# SCH_IV_Project_2025-03-30.net
KiCad netlist of a schematic drawn in EasyEDA
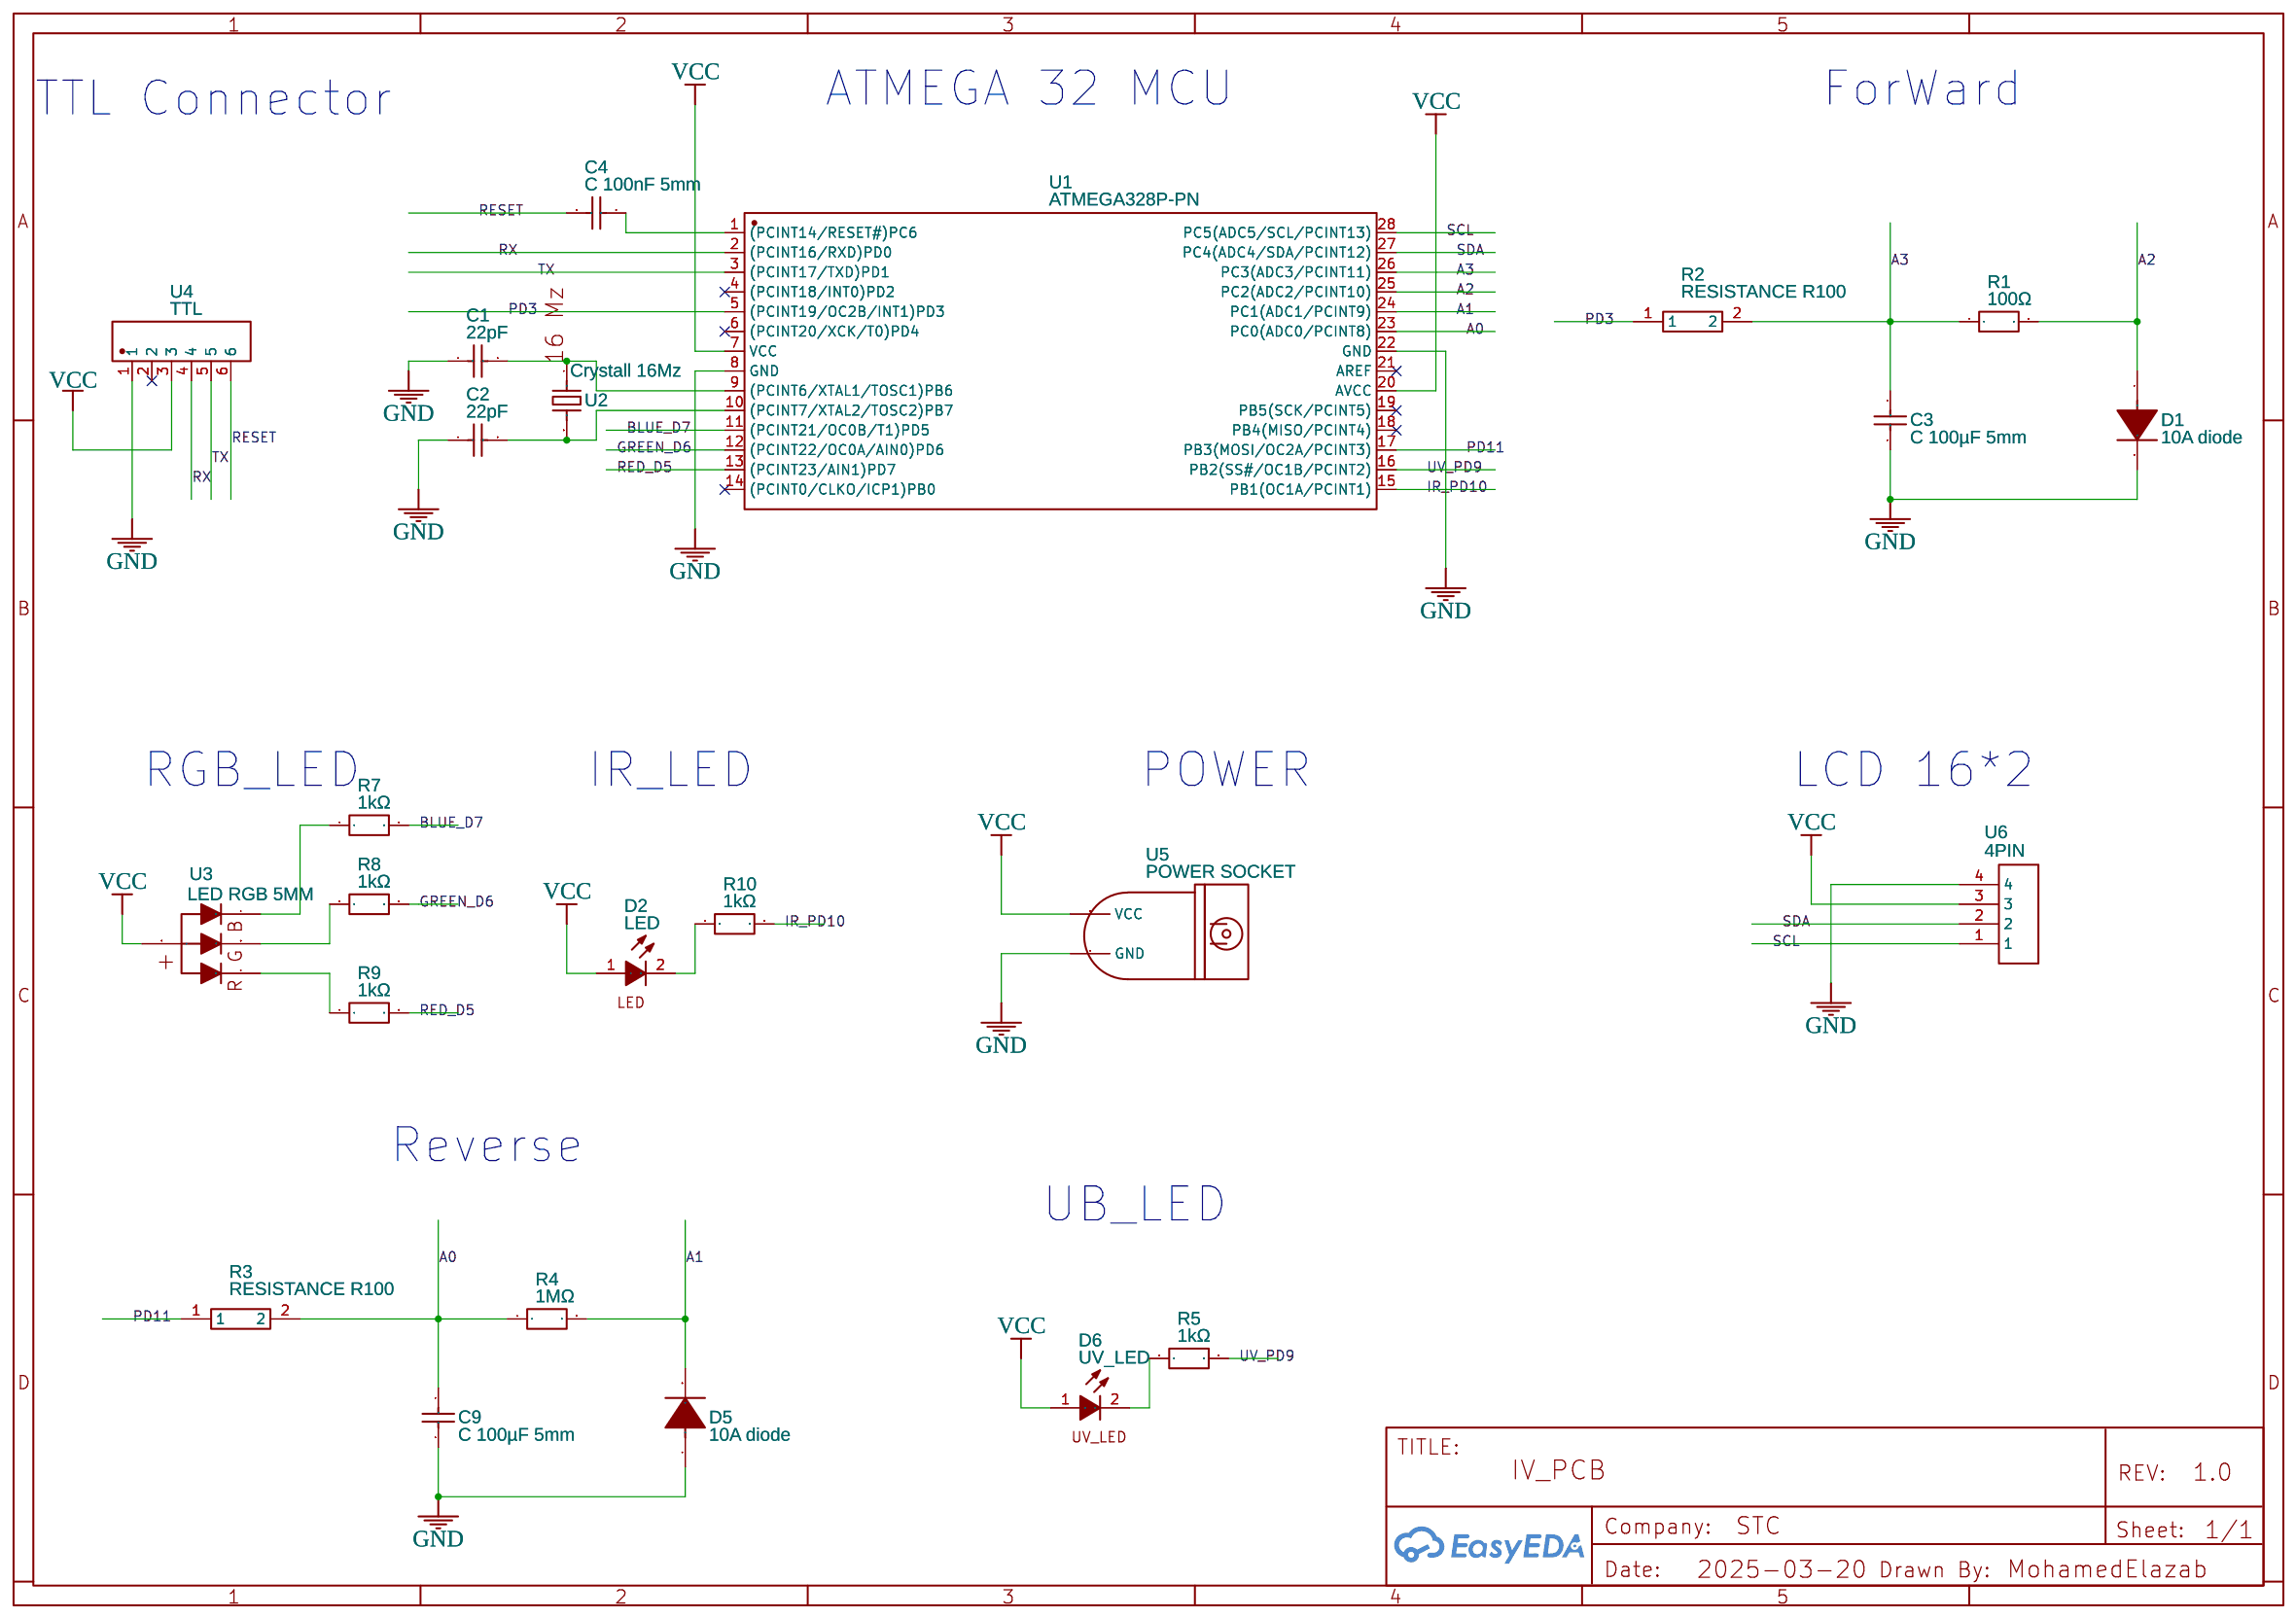
[diagram p0: schematic sheet]

(export (version "E")
  (design (tool "Eeschema 10.0.6"))
  (components
    (comp (ref "C1")
      (value "22pF")
      (fields (field (name "Manufacturer Part") "22pf/50V 10%") (field (name "Manufacturer") "ReliaPro"))
      (libsource (lib "") (part "22pf/50V 10%"))
    )
    (comp (ref "C2")
      (value "22pF")
      (fields (field (name "Manufacturer Part") "22pf/50V 10%") (field (name "Manufacturer") "ReliaPro"))
      (libsource (lib "") (part "22pf/50V 10%"))
    )
    (comp (ref "C3")
      (value "C 100µF 5mm")
      (fields (field (name "Manufacturer Part") "0.1UF(104) +-20% 63v") (field (name "Manufacturer") "LCSC"))
      (libsource (lib "") (part "C 100nF 5mm_1"))
    )
    (comp (ref "C4")
      (value "C 100nF 5mm")
      (fields (field (name "Manufacturer Part") "0.1UF(104) +-20% 63v") (field (name "Manufacturer") "LCSC"))
      (libsource (lib "") (part "C 100nF 5mm"))
    )
    (comp (ref "C9")
      (value "C 100µF 5mm")
      (fields (field (name "Manufacturer Part") "0.1UF(104) +-20% 63v") (field (name "Manufacturer") "LCSC"))
      (libsource (lib "") (part "C 100nF 5mm_1"))
    )
    (comp (ref "D1")
      (value "10A diode")
      (fields (field (name "Manufacturer Part") "10A10") (field (name "Manufacturer") "ST(先科)"))
      (libsource (lib "") (part "10A diode_1"))
    )
    (comp (ref "D2")
      (value "LED")
      (fields (field (name "Manufacturer Part") "5600") (field (name "Manufacturer") "VccLite"))
      (libsource (lib "") (part "LED_1"))
    )
    (comp (ref "D5")
      (value "10A diode")
      (fields (field (name "Manufacturer Part") "10A10") (field (name "Manufacturer") "ST(先科)"))
      (libsource (lib "") (part "10A diode"))
    )
    (comp (ref "D6")
      (value "UV_LED")
      (fields (field (name "Manufacturer Part") "5600") (field (name "Manufacturer") "VccLite"))
      (libsource (lib "") (part "LED"))
    )
    (comp (ref "R1")
      (value "100Ω")
      (fields (field (name "Manufacturer Part") "MFR50SFBE52-1K") (field (name "Manufacturer") "YAGEO(国巨)"))
      (libsource (lib "") (part "MFR50SFBE52-1K"))
    )
    (comp (ref "R2") (value "RESISTANCE R100") (libsource (lib "") (part "RESISTANCE R100")))
    (comp (ref "R3") (value "RESISTANCE R100") (libsource (lib "") (part "RESISTANCE R100")))
    (comp (ref "R4")
      (value "1MΩ")
      (fields (field (name "Manufacturer Part") "MFR50SFBE52-1K") (field (name "Manufacturer") "YAGEO(国巨)"))
      (libsource (lib "") (part "MFR50SFBE52-1K"))
    )
    (comp (ref "R5")
      (value "1kΩ")
      (fields (field (name "Manufacturer Part") "MFR50SFBE52-1K") (field (name "Manufacturer") "YAGEO(国巨)"))
      (libsource (lib "") (part "MFR50SFBE52-1K"))
    )
    (comp (ref "R7")
      (value "1kΩ")
      (fields (field (name "Manufacturer Part") "MFR50SFBE52-1K") (field (name "Manufacturer") "YAGEO(国巨)"))
      (libsource (lib "") (part "MFR50SFBE52-1K"))
    )
    (comp (ref "R8")
      (value "1kΩ")
      (fields (field (name "Manufacturer Part") "MFR50SFBE52-1K") (field (name "Manufacturer") "YAGEO(国巨)"))
      (libsource (lib "") (part "MFR50SFBE52-1K"))
    )
    (comp (ref "R9")
      (value "1kΩ")
      (fields (field (name "Manufacturer Part") "MFR50SFBE52-1K") (field (name "Manufacturer") "YAGEO(国巨)"))
      (libsource (lib "") (part "MFR50SFBE52-1K"))
    )
    (comp (ref "R10")
      (value "1kΩ")
      (fields (field (name "Manufacturer Part") "MFR50SFBE52-1K") (field (name "Manufacturer") "YAGEO(国巨)"))
      (libsource (lib "") (part "MFR50SFBE52-1K"))
    )
    (comp (ref "U1")
      (value "ATMEGA328P-PN")
      (fields (field (name "Manufacturer") "MICROCHIP(美国微芯)"))
      (libsource (lib "") (part "ATMEGA328P-PN"))
    )
    (comp (ref "U2") (value "Crystall 16Mz") (libsource (lib "") (part "Crystall 16Mz")))
    (comp (ref "U3") (value "LED RGB 5MM") (libsource (lib "") (part "LED RGB 5MM (ARL5RGB) EDIT")))
    (comp (ref "U4")
      (value "TTL")
      (fields (field (name "Manufacturer Part") "DS1021-1x6SF11-B") (field (name "Manufacturer") "CONNFLY"))
      (libsource (lib "") (part "DS1021-1X6SF11-B"))
    )
    (comp (ref "U5") (value "POWER SOCKET") (libsource (lib "") (part "POWER SOCKET")))
    (comp (ref "U6") (value "4PIN") (libsource (lib "") (part "4PIN")))
  )
  (nets
    (net (code "1") (name "/A0") (class "Default")
      (node (ref "C9") (pin "1") (pinfunction "1_1") (pintype "input"))
      (node (ref "R3") (pin "2") (pinfunction "2_2") (pintype "unspecified"))
      (node (ref "R4") (pin "1") (pinfunction "1_1") (pintype "unspecified"))
      (node (ref "U1") (pin "23") (pinfunction "PC0(ADC0/PCINT8)_23") (pintype "unspecified"))
    )
    (net (code "2") (name "/A1") (class "Default")
      (node (ref "D5") (pin "2") (pinfunction "K_2") (pintype "unspecified"))
      (node (ref "R4") (pin "2") (pinfunction "2_2") (pintype "unspecified"))
      (node (ref "U1") (pin "24") (pinfunction "PC1(ADC1/PCINT9)_24") (pintype "unspecified"))
    )
    (net (code "3") (name "/A2") (class "Default")
      (node (ref "D1") (pin "1") (pinfunction "A_1") (pintype "unspecified"))
      (node (ref "R1") (pin "2") (pinfunction "2_2") (pintype "unspecified"))
      (node (ref "U1") (pin "25") (pinfunction "PC2(ADC2/PCINT10)_25") (pintype "unspecified"))
    )
    (net (code "4") (name "/A3") (class "Default")
      (node (ref "C3") (pin "1") (pinfunction "1_1") (pintype "input"))
      (node (ref "R1") (pin "1") (pinfunction "1_1") (pintype "unspecified"))
      (node (ref "R2") (pin "2") (pinfunction "2_2") (pintype "unspecified"))
      (node (ref "U1") (pin "26") (pinfunction "PC3(ADC3/PCINT11)_26") (pintype "unspecified"))
    )
    (net (code "5") (name "/BLUE_D7") (class "Default")
      (node (ref "R7") (pin "2") (pinfunction "2_2") (pintype "unspecified"))
      (node (ref "U1") (pin "11") (pinfunction "(PCINT21/OC0B/T1)PD5_11") (pintype "unspecified"))
    )
    (net (code "6") (name "/GREEN_D6") (class "Default")
      (node (ref "R8") (pin "2") (pinfunction "2_2") (pintype "unspecified"))
      (node (ref "U1") (pin "12") (pinfunction "(PCINT22/OC0A/AIN0)PD6_12") (pintype "unspecified"))
    )
    (net (code "7") (name "/IR_PD10") (class "Default")
      (node (ref "R10") (pin "2") (pinfunction "2_2") (pintype "unspecified"))
      (node (ref "U1") (pin "15") (pinfunction "PB1(OC1A/PCINT1)_15") (pintype "unspecified"))
    )
    (net (code "8") (name "/PD3") (class "Default")
      (node (ref "R2") (pin "1") (pinfunction "1_1") (pintype "unspecified"))
      (node (ref "U1") (pin "5") (pinfunction "(PCINT19/OC2B/INT1)PD3_5") (pintype "unspecified"))
    )
    (net (code "9") (name "/PD11") (class "Default")
      (node (ref "R3") (pin "1") (pinfunction "1_1") (pintype "unspecified"))
      (node (ref "U1") (pin "17") (pinfunction "PB3(MOSI/OC2A/PCINT3)_17") (pintype "unspecified"))
    )
    (net (code "10") (name "/RED_D5") (class "Default")
      (node (ref "R9") (pin "2") (pinfunction "2_2") (pintype "unspecified"))
      (node (ref "U1") (pin "13") (pinfunction "(PCINT23/AIN1)PD7_13") (pintype "unspecified"))
    )
    (net (code "11") (name "/RESET") (class "Default")
      (node (ref "C4") (pin "1") (pinfunction "1_1") (pintype "input"))
      (node (ref "U4") (pin "6") (pinfunction "6_6") (pintype "unspecified"))
    )
    (net (code "12") (name "/RX") (class "Default")
      (node (ref "U1") (pin "2") (pinfunction "(PCINT16/RXD)PD0_2") (pintype "unspecified"))
      (node (ref "U4") (pin "4") (pinfunction "4_4") (pintype "unspecified"))
    )
    (net (code "13") (name "/SCL") (class "Default")
      (node (ref "U1") (pin "28") (pinfunction "PC5(ADC5/SCL/PCINT13)_28") (pintype "unspecified"))
      (node (ref "U6") (pin "1") (pinfunction "1_1") (pintype "unspecified"))
    )
    (net (code "14") (name "/SDA") (class "Default")
      (node (ref "U1") (pin "27") (pinfunction "PC4(ADC4/SDA/PCINT12)_27") (pintype "unspecified"))
      (node (ref "U6") (pin "2") (pinfunction "2_2") (pintype "unspecified"))
    )
    (net (code "15") (name "/TX") (class "Default")
      (node (ref "U1") (pin "3") (pinfunction "(PCINT17/TXD)PD1_3") (pintype "unspecified"))
      (node (ref "U4") (pin "5") (pinfunction "5_5") (pintype "unspecified"))
    )
    (net (code "16") (name "/UV_PD9") (class "Default")
      (node (ref "R5") (pin "2") (pinfunction "2_2") (pintype "unspecified"))
      (node (ref "U1") (pin "16") (pinfunction "PB2(SS#/OC1B/PCINT2)_16") (pintype "unspecified"))
    )
    (net (code "17") (name "GND") (class "Default")
      (node (ref "C1") (pin "1") (pinfunction "1_1") (pintype "input"))
      (node (ref "C2") (pin "1") (pinfunction "1_1") (pintype "input"))
      (node (ref "C3") (pin "2") (pinfunction "2_2") (pintype "input"))
      (node (ref "C9") (pin "2") (pinfunction "2_2") (pintype "input"))
      (node (ref "D1") (pin "2") (pinfunction "K_2") (pintype "unspecified"))
      (node (ref "D5") (pin "1") (pinfunction "A_1") (pintype "unspecified"))
      (node (ref "U1") (pin "22") (pinfunction "GND_22") (pintype "unspecified"))
      (node (ref "U1") (pin "8") (pinfunction "GND_8") (pintype "unspecified"))
      (node (ref "U4") (pin "1") (pinfunction "1_1") (pintype "unspecified"))
      (node (ref "U5") (pin "2") (pinfunction "GND_2") (pintype "passive"))
      (node (ref "U6") (pin "4") (pinfunction "4_4") (pintype "unspecified"))
    )
    (net (code "18") (name "Net-(D2-K)") (class "Default")
      (node (ref "D2") (pin "2") (pinfunction "K_2") (pintype "input"))
      (node (ref "R10") (pin "1") (pinfunction "1_1") (pintype "unspecified"))
    )
    (net (code "19") (name "Net-(D6-K)") (class "Default")
      (node (ref "D6") (pin "2") (pinfunction "K_2") (pintype "input"))
      (node (ref "R5") (pin "1") (pinfunction "1_1") (pintype "unspecified"))
    )
    (net (code "20") (name "Net-(R9-Pad1)") (class "Default")
      (node (ref "R9") (pin "1") (pinfunction "1_1") (pintype "unspecified"))
      (node (ref "U3") (pin "1") (pinfunction "1_1") (pintype "unspecified"))
    )
    (net (code "21") (name "Net-(U1-(PCINT6{slash}XTAL1{slash}TOSC1)PB6)") (class "Default")
      (node (ref "C1") (pin "2") (pinfunction "2_2") (pintype "input"))
      (node (ref "U1") (pin "9") (pinfunction "(PCINT6/XTAL1/TOSC1)PB6_9") (pintype "unspecified"))
      (node (ref "U2") (pin "1") (pinfunction "1_1") (pintype "input"))
    )
    (net (code "22") (name "Net-(U1-(PCINT7{slash}XTAL2{slash}TOSC2)PB7)") (class "Default")
      (node (ref "C2") (pin "2") (pinfunction "2_2") (pintype "input"))
      (node (ref "U1") (pin "10") (pinfunction "(PCINT7/XTAL2/TOSC2)PB7_10") (pintype "unspecified"))
      (node (ref "U2") (pin "2") (pinfunction "2_2") (pintype "input"))
    )
    (net (code "23") (name "Net-(U1-(PCINT14{slash}RESET#)PC6)") (class "Default")
      (node (ref "C4") (pin "2") (pinfunction "2_2") (pintype "input"))
      (node (ref "U1") (pin "1") (pinfunction "(PCINT14/RESET#)PC6_1") (pintype "unspecified"))
    )
    (net (code "24") (name "Net-(U3-2)") (class "Default")
      (node (ref "R8") (pin "1") (pinfunction "1_1") (pintype "unspecified"))
      (node (ref "U3") (pin "3") (pinfunction "2_3") (pintype "unspecified"))
    )
    (net (code "25") (name "Net-(U3-3)") (class "Default")
      (node (ref "R7") (pin "1") (pinfunction "1_1") (pintype "unspecified"))
      (node (ref "U3") (pin "4") (pinfunction "3_4") (pintype "unspecified"))
    )
    (net (code "26") (name "VCC") (class "Default")
      (node (ref "D2") (pin "1") (pinfunction "A_1") (pintype "input"))
      (node (ref "D6") (pin "1") (pinfunction "A_1") (pintype "input"))
      (node (ref "U1") (pin "20") (pinfunction "AVCC_20") (pintype "unspecified"))
      (node (ref "U1") (pin "7") (pinfunction "VCC_7") (pintype "unspecified"))
      (node (ref "U3") (pin "2") (pinfunction "4_2") (pintype "unspecified"))
      (node (ref "U4") (pin "3") (pinfunction "3_3") (pintype "unspecified"))
      (node (ref "U5") (pin "1") (pinfunction "VCC_1") (pintype "passive"))
      (node (ref "U6") (pin "3") (pinfunction "3_3") (pintype "unspecified"))
    )
    (net (code "27") (name "unconnected-(U1-(PCINT0{slash}CLKO{slash}ICP1)PB0-Pad14)") (class "Default")
      (node (ref "U1") (pin "14") (pinfunction "(PCINT0/CLKO/ICP1)PB0_14") (pintype "unspecified+no_connect"))
    )
    (net (code "28") (name "unconnected-(U1-(PCINT18{slash}INT0)PD2-Pad4)") (class "Default")
      (node (ref "U1") (pin "4") (pinfunction "(PCINT18/INT0)PD2_4") (pintype "unspecified+no_connect"))
    )
    (net (code "29") (name "unconnected-(U1-(PCINT20{slash}XCK{slash}T0)PD4-Pad6)") (class "Default")
      (node (ref "U1") (pin "6") (pinfunction "(PCINT20/XCK/T0)PD4_6") (pintype "unspecified+no_connect"))
    )
    (net (code "30") (name "unconnected-(U1-AREF-Pad21)") (class "Default")
      (node (ref "U1") (pin "21") (pinfunction "AREF_21") (pintype "unspecified+no_connect"))
    )
    (net (code "31") (name "unconnected-(U1-PB4(MISO{slash}PCINT4)-Pad18)") (class "Default")
      (node (ref "U1") (pin "18") (pinfunction "PB4(MISO/PCINT4)_18") (pintype "unspecified+no_connect"))
    )
    (net (code "32") (name "unconnected-(U1-PB5(SCK{slash}PCINT5)-Pad19)") (class "Default")
      (node (ref "U1") (pin "19") (pinfunction "PB5(SCK/PCINT5)_19") (pintype "unspecified+no_connect"))
    )
    (net (code "33") (name "unconnected-(U4-Pad2)") (class "Default")
      (node (ref "U4") (pin "2") (pinfunction "2_2") (pintype "unspecified+no_connect"))
    )
  )
)
